# SCH_Personal-NFC_2026-05-23.net
KiCad netlist of a schematic drawn in EasyEDA
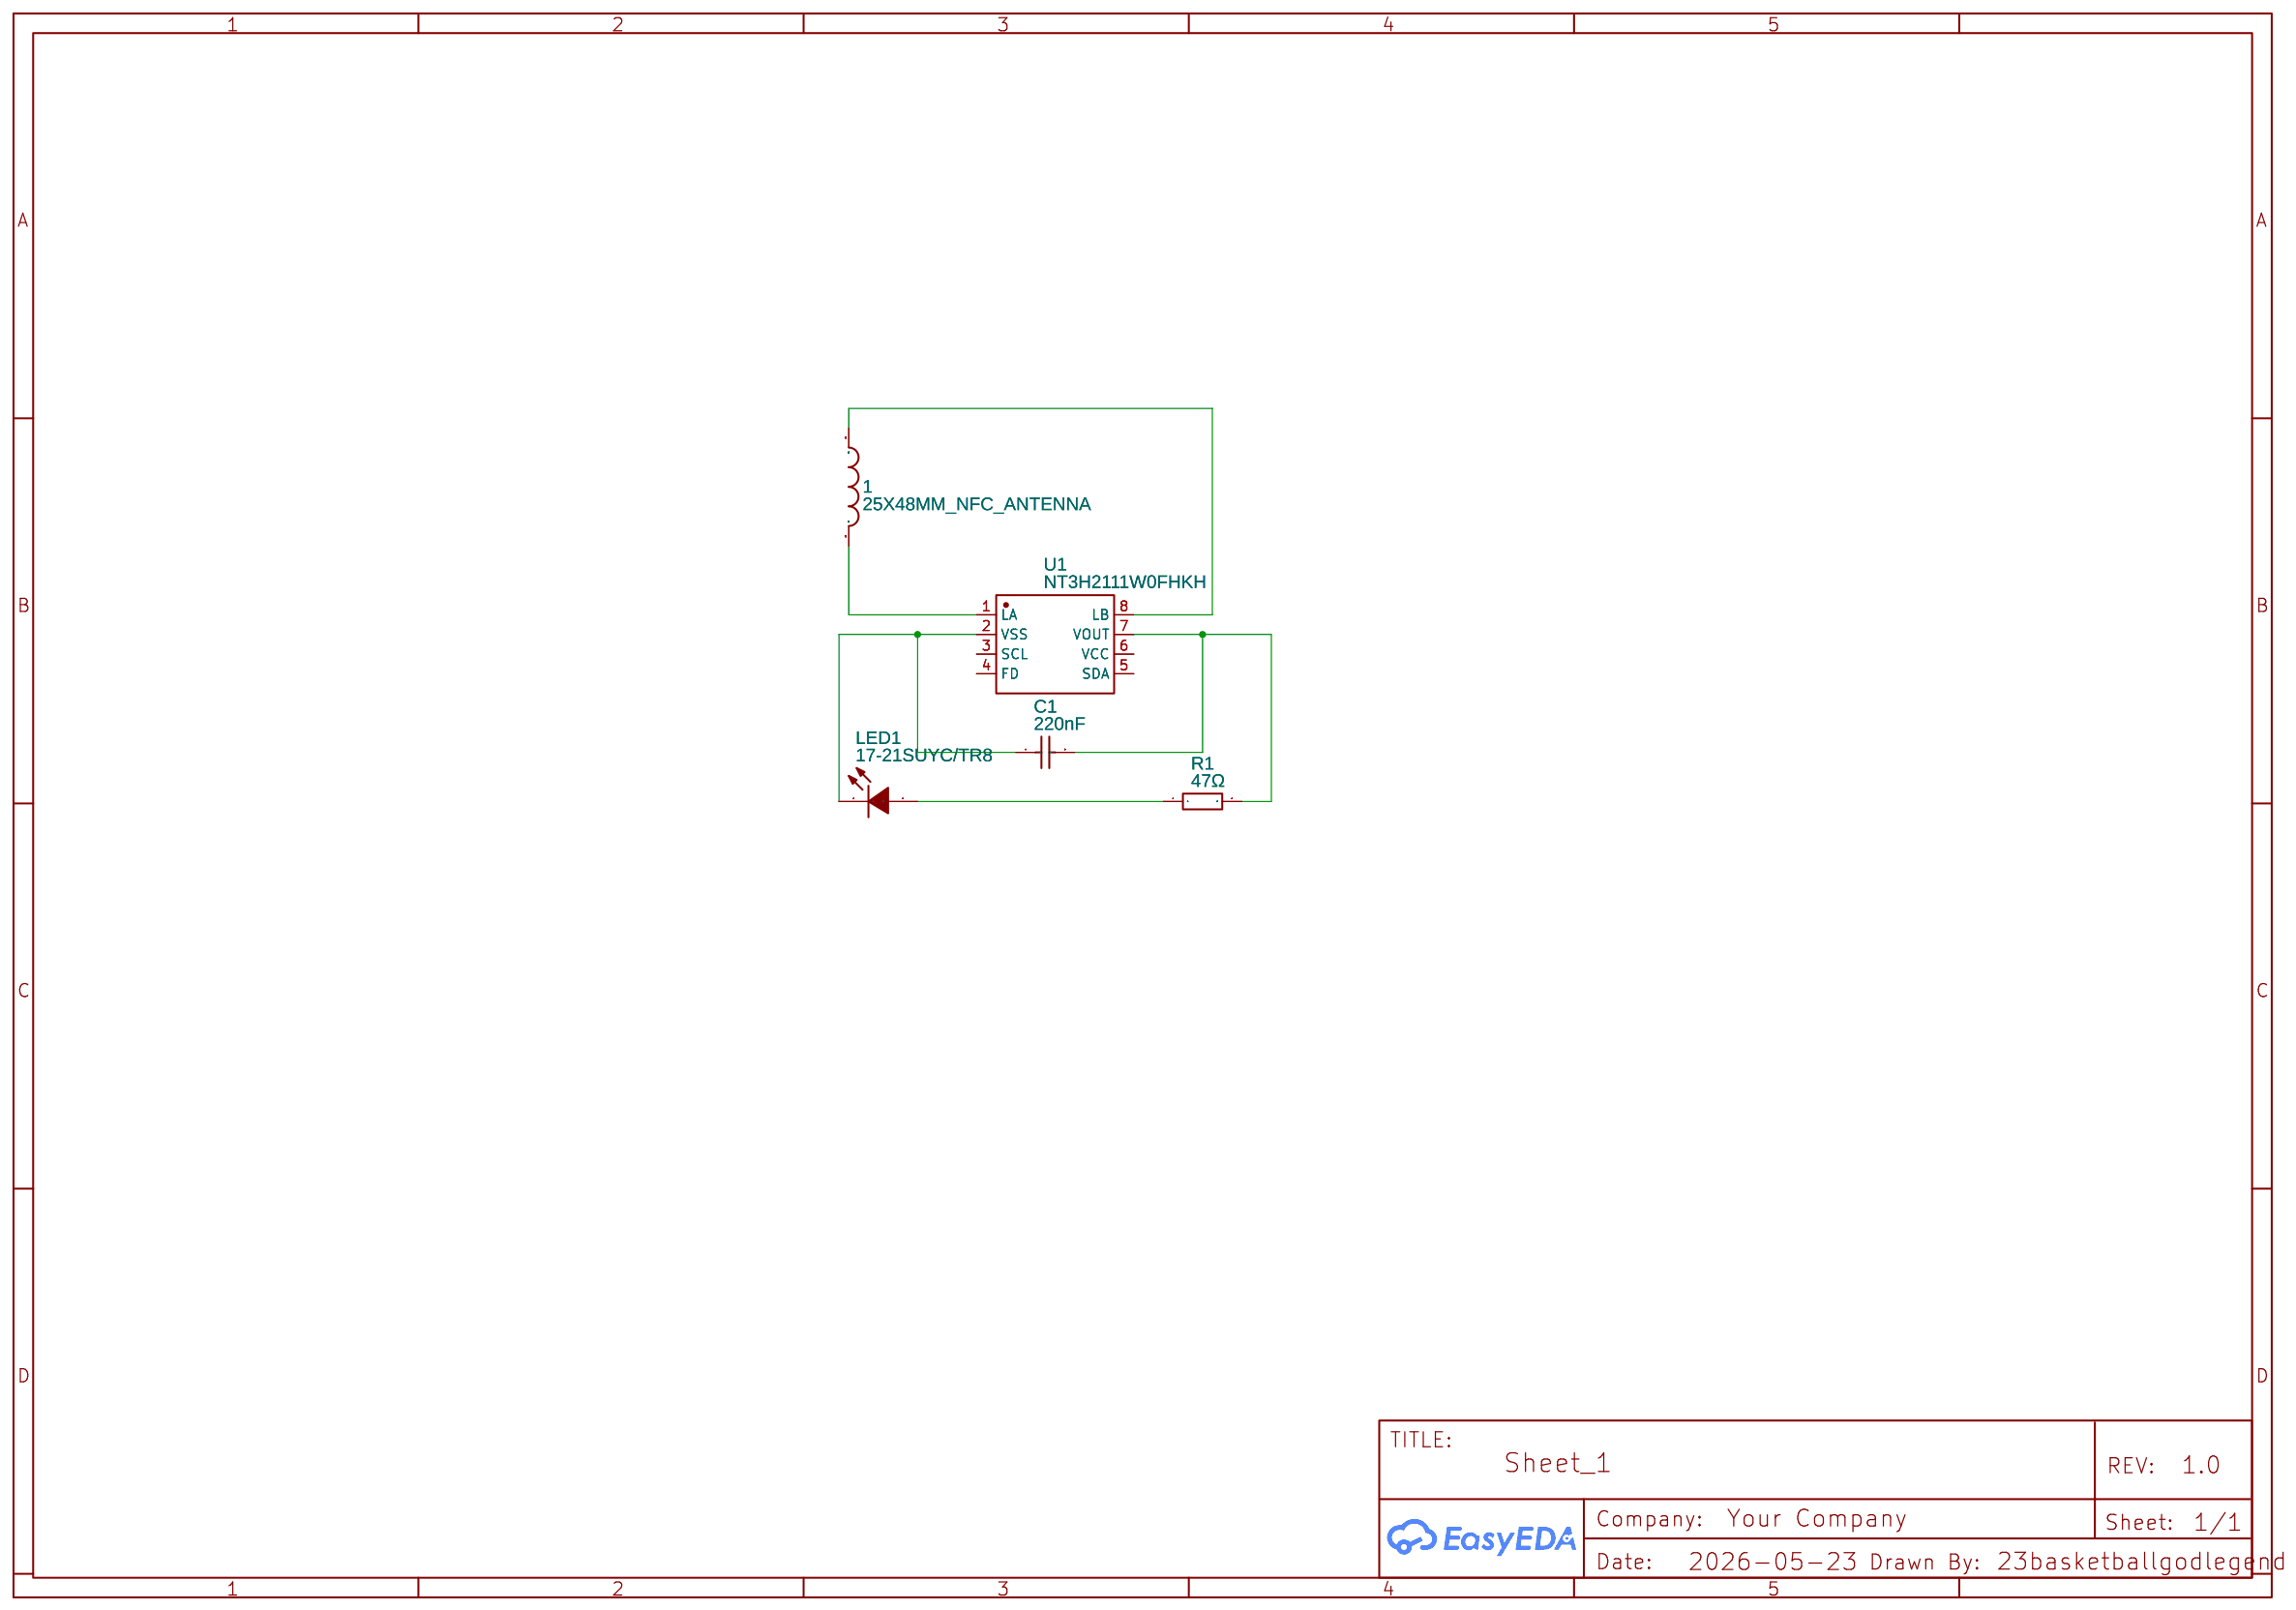
[diagram p0: schematic sheet]

(export (version "E")
  (design (tool "Eeschema 10.0.6"))
  (components
    (comp (ref "1") (value "25X48MM_NFC_ANTENNA") (libsource (lib "") (part "25X48MM_NFC_ANTENNA")))
    (comp (ref "C1")
      (value "220nF")
      (fields
        (field (name "Manufacturer Part") "CL10B224KA8NNNC")
        (field (name "Manufacturer") "SAMSUNG(三星)")
      )
      (libsource (lib "") (part "CL10B224KA8NNNC"))
    )
    (comp (ref "LED1")
      (value "17-21SUYC/TR8")
      (fields (field (name "Manufacturer Part") "KT-0805黄灯") (field (name "Manufacturer") "KENTO"))
      (libsource (lib "") (part "17-21SUYC/TR8"))
    )
    (comp (ref "R1")
      (value "47Ω")
      (fields
        (field (name "Manufacturer Part") "0603WAF470JT5E")
        (field (name "Manufacturer") "UNI-ROYAL(厚声)")
      )
      (libsource (lib "") (part "0603WAF470JT5E"))
    )
    (comp (ref "U1")
      (value "NT3H2111W0FHKH")
      (fields (field (name "Manufacturer") "NXP(恩智浦)"))
      (libsource (lib "") (part "NT3H2111W0FHKH"))
    )
  )
  (nets
    (net (code "1") (name "Net-(LED1-+)") (class "Default")
      (node (ref "LED1") (pin "1") (pinfunction "+_1") (pintype "unspecified"))
      (node (ref "R1") (pin "1") (pinfunction "1_1") (pintype "input"))
    )
    (net (code "2") (name "Net-(LED1--)") (class "Default")
      (node (ref "C1") (pin "1") (pinfunction "1_1") (pintype "input"))
      (node (ref "LED1") (pin "2") (pinfunction "-_2") (pintype "unspecified"))
      (node (ref "U1") (pin "2") (pinfunction "VSS_2") (pintype "unspecified"))
    )
    (net (code "3") (name "Net-(U1-LA)") (class "Default")
      (node (ref "1") (pin "P$2") (pinfunction "P$2_P$2") (pintype "bidirectional"))
      (node (ref "U1") (pin "1") (pinfunction "LA_1") (pintype "unspecified"))
    )
    (net (code "4") (name "Net-(U1-LB)") (class "Default")
      (node (ref "1") (pin "P$1") (pinfunction "P$1_P$1") (pintype "bidirectional"))
      (node (ref "U1") (pin "8") (pinfunction "LB_8") (pintype "unspecified"))
    )
    (net (code "5") (name "Net-(U1-VOUT)") (class "Default")
      (node (ref "C1") (pin "2") (pinfunction "2_2") (pintype "input"))
      (node (ref "R1") (pin "2") (pinfunction "2_2") (pintype "input"))
      (node (ref "U1") (pin "7") (pinfunction "VOUT_7") (pintype "unspecified"))
    )
    (net (code "6") (name "unconnected-(U1-FD-Pad4)") (class "Default")
      (node (ref "U1") (pin "4") (pinfunction "FD_4") (pintype "unspecified"))
    )
    (net (code "7") (name "unconnected-(U1-SCL-Pad3)") (class "Default")
      (node (ref "U1") (pin "3") (pinfunction "SCL_3") (pintype "unspecified"))
    )
    (net (code "8") (name "unconnected-(U1-SDA-Pad5)") (class "Default")
      (node (ref "U1") (pin "5") (pinfunction "SDA_5") (pintype "unspecified"))
    )
    (net (code "9") (name "unconnected-(U1-VCC-Pad6)") (class "Default")
      (node (ref "U1") (pin "6") (pinfunction "VCC_6") (pintype "unspecified"))
    )
  )
)
